# Rear_right_lamp_v4.net
KiCad netlist of a schematic drawn in EAGLE
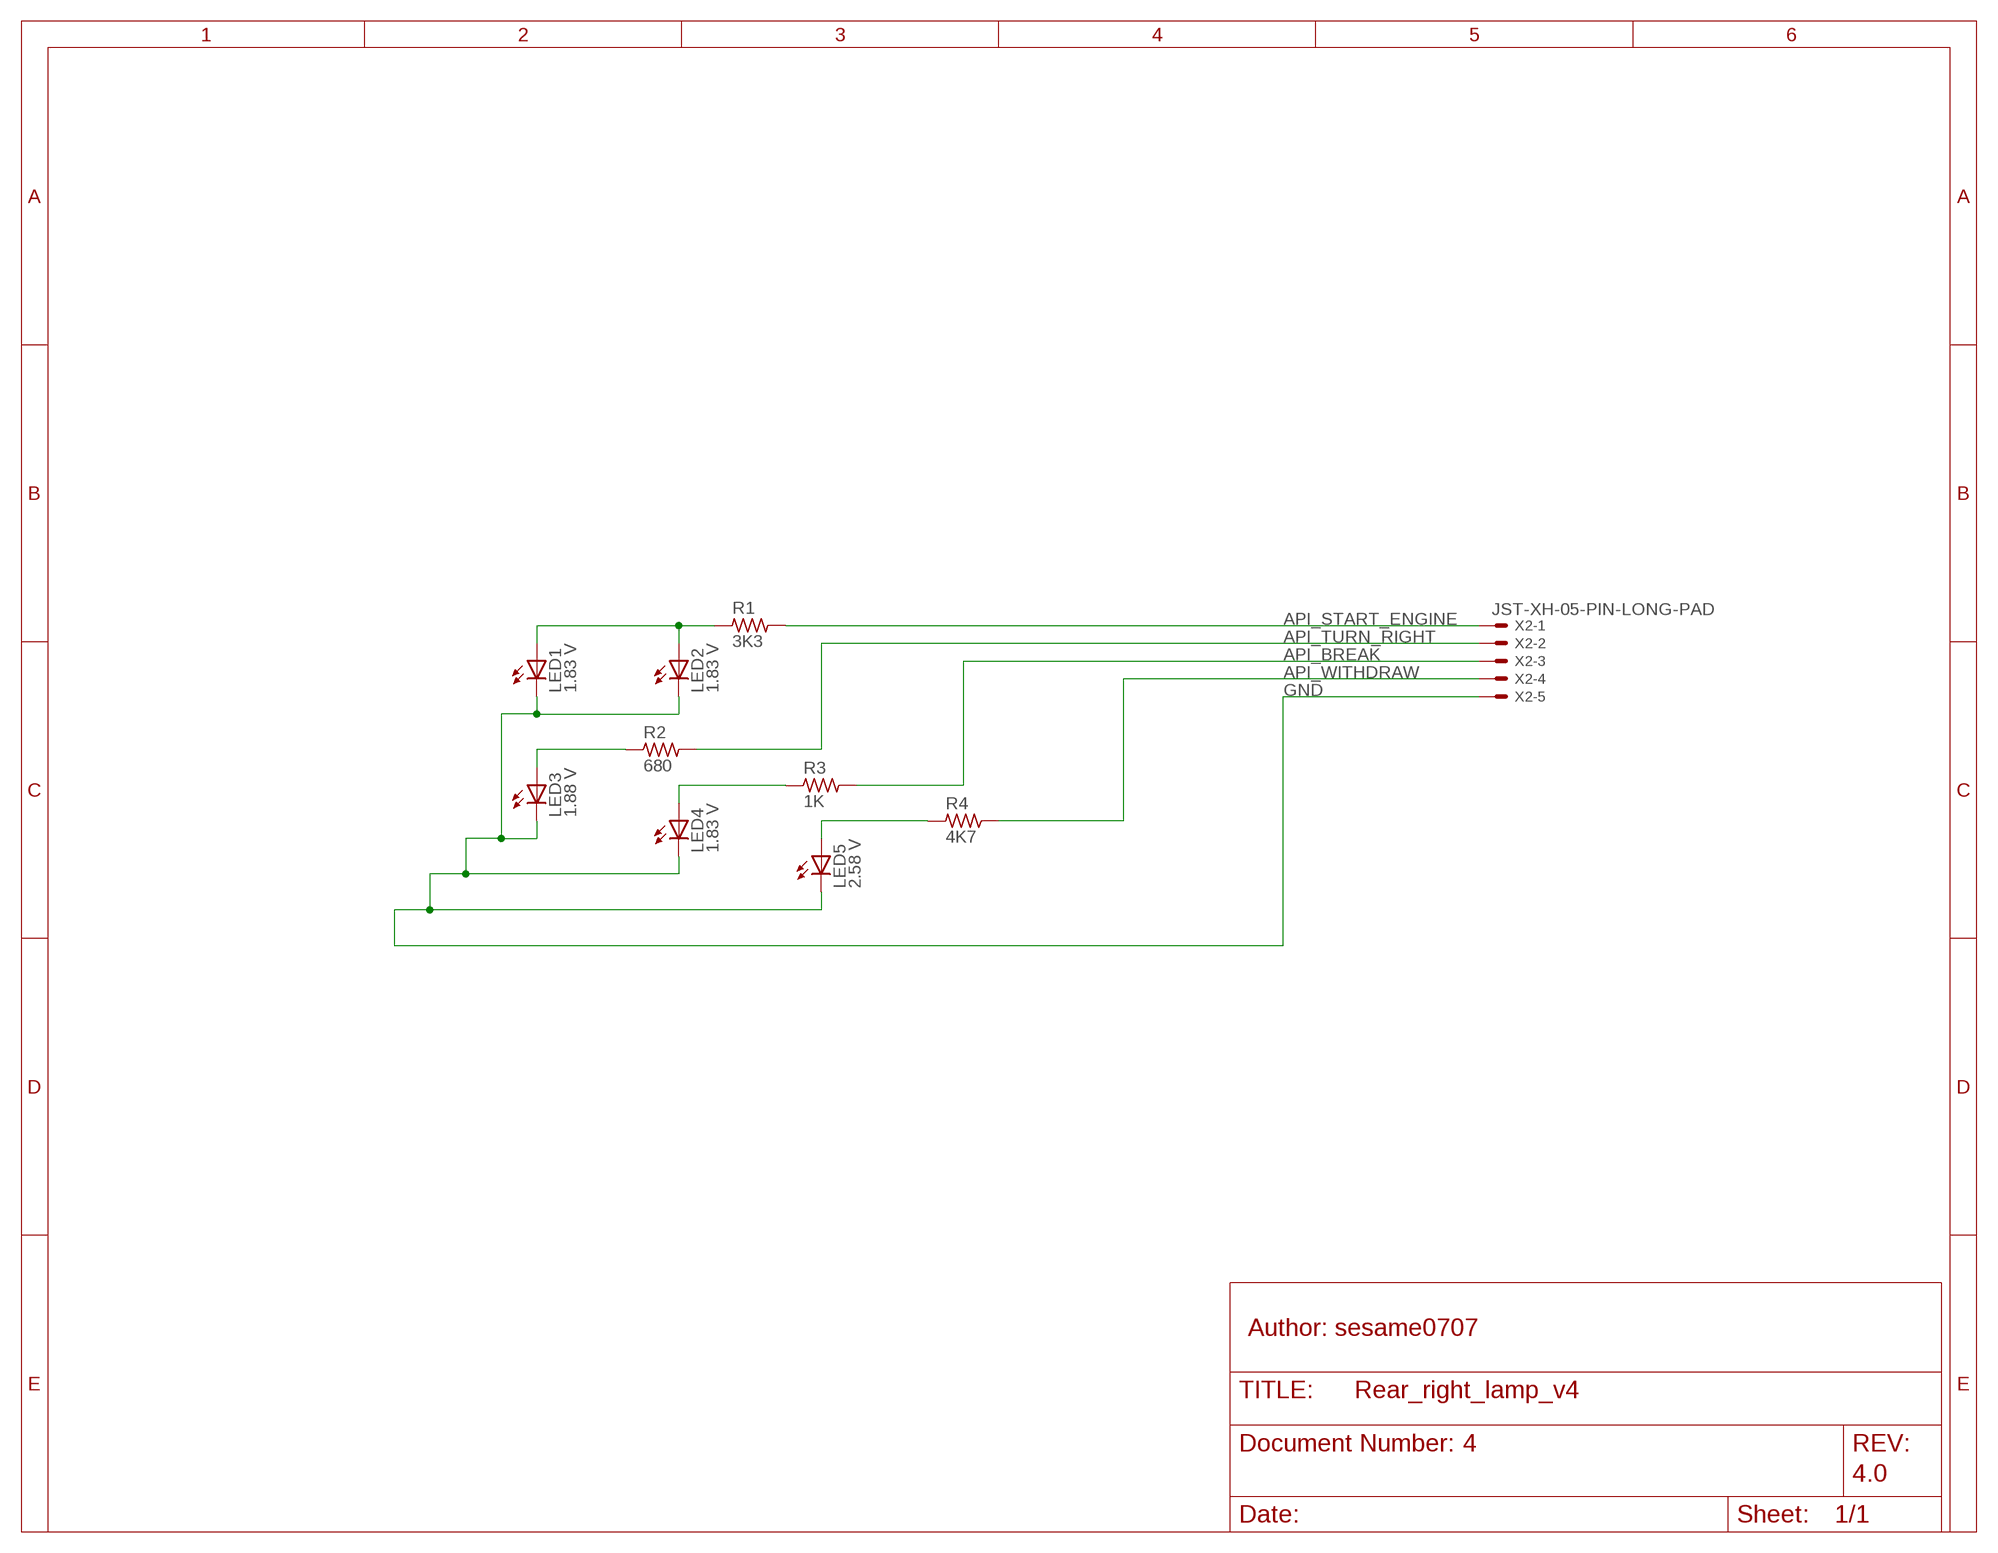
[diagram p0: schematic, sheet 1]

(export (version "E")
  (design (tool "Eeschema 10.0.6"))
  (components
    (comp (ref "LED1")
      (value "1.83 V")
      (footprint "eagle-import:LED5MM")
      (libsource (lib "eagle-import") (part "LED5MM"))
    )
    (comp (ref "LED2")
      (value "1.83 V")
      (footprint "eagle-import:LED5MM")
      (libsource (lib "eagle-import") (part "LED5MM"))
    )
    (comp (ref "LED3")
      (value "1.88 V")
      (footprint "eagle-import:LED5MM")
      (libsource (lib "eagle-import") (part "LED5MM"))
    )
    (comp (ref "LED4")
      (value "1.83 V")
      (footprint "eagle-import:LED5MM")
      (libsource (lib "eagle-import") (part "LED5MM"))
    )
    (comp (ref "LED5")
      (value "2.58 V")
      (footprint "eagle-import:LED5MM")
      (libsource (lib "eagle-import") (part "LED5MM"))
    )
    (comp (ref "R1")
      (value "3K3")
      (footprint "eagle-import:R1206")
      (libsource (lib "eagle-import") (part "R_1206"))
    )
    (comp (ref "R2")
      (value "680")
      (footprint "eagle-import:R1206")
      (libsource (lib "eagle-import") (part "R_1206"))
    )
    (comp (ref "R3")
      (value "1K")
      (footprint "eagle-import:R1206")
      (libsource (lib "eagle-import") (part "R_1206"))
    )
    (comp (ref "R4")
      (value "4K7")
      (footprint "eagle-import:R1206")
      (libsource (lib "eagle-import") (part "R_1206"))
    )
    (comp (ref "X2")
      (value "JST-XH-05-PIN-LONG-PAD")
      (footprint "eagle-import:JST-XH-05-PACKAGE-LONG-PAD")
      (libsource (lib "eagle-import") (part "JST-XH-05-PIN-LONG-PAD"))
    )
  )
  (nets
    (net (code "1") (name "/API_BREAK") (class "Default")
      (node (ref "R3") (pin "2") (pinfunction "2_2") (pintype "passive"))
      (node (ref "X2") (pin "3") (pinfunction "S_3") (pintype "passive"))
    )
    (net (code "2") (name "/API_START_ENGINE") (class "Default")
      (node (ref "LED1") (pin "A") (pinfunction "A_A") (pintype "passive"))
      (node (ref "LED2") (pin "A") (pinfunction "A_A") (pintype "passive"))
      (node (ref "R1") (pin "1") (pinfunction "1_1") (pintype "passive"))
    )
    (net (code "3") (name "/API_TURN_RIGHT") (class "Default")
      (node (ref "R2") (pin "2") (pinfunction "2_2") (pintype "passive"))
      (node (ref "X2") (pin "2") (pinfunction "S_2") (pintype "passive"))
    )
    (net (code "4") (name "/API_WITHDRAW") (class "Default")
      (node (ref "R4") (pin "2") (pinfunction "2_2") (pintype "passive"))
      (node (ref "X2") (pin "4") (pinfunction "S_4") (pintype "passive"))
    )
    (net (code "5") (name "/GND") (class "Default")
      (node (ref "LED1") (pin "K") (pinfunction "C_K") (pintype "passive"))
      (node (ref "LED2") (pin "K") (pinfunction "C_K") (pintype "passive"))
      (node (ref "LED3") (pin "K") (pinfunction "C_K") (pintype "passive"))
      (node (ref "LED4") (pin "K") (pinfunction "C_K") (pintype "passive"))
      (node (ref "LED5") (pin "K") (pinfunction "C_K") (pintype "passive"))
      (node (ref "X2") (pin "5") (pinfunction "S_5") (pintype "passive"))
    )
    (net (code "6") (name "Net-(LED3-PadA)") (class "Default")
      (node (ref "LED3") (pin "A") (pinfunction "A_A") (pintype "passive"))
      (node (ref "R2") (pin "1") (pinfunction "1_1") (pintype "passive"))
    )
    (net (code "7") (name "Net-(LED4-PadA)") (class "Default")
      (node (ref "LED4") (pin "A") (pinfunction "A_A") (pintype "passive"))
      (node (ref "R3") (pin "1") (pinfunction "1_1") (pintype "passive"))
    )
    (net (code "8") (name "Net-(LED5-PadA)") (class "Default")
      (node (ref "LED5") (pin "A") (pinfunction "A_A") (pintype "passive"))
      (node (ref "R4") (pin "1") (pinfunction "1_1") (pintype "passive"))
    )
    (net (code "9") (name "Net-(X2A-S)") (class "Default")
      (node (ref "R1") (pin "2") (pinfunction "2_2") (pintype "passive"))
      (node (ref "X2") (pin "1") (pinfunction "S_1") (pintype "passive"))
    )
  )
)
